# SCH_ELLIE_DISPLAY_PANEL.net
KiCad netlist of a schematic drawn in EasyEDA
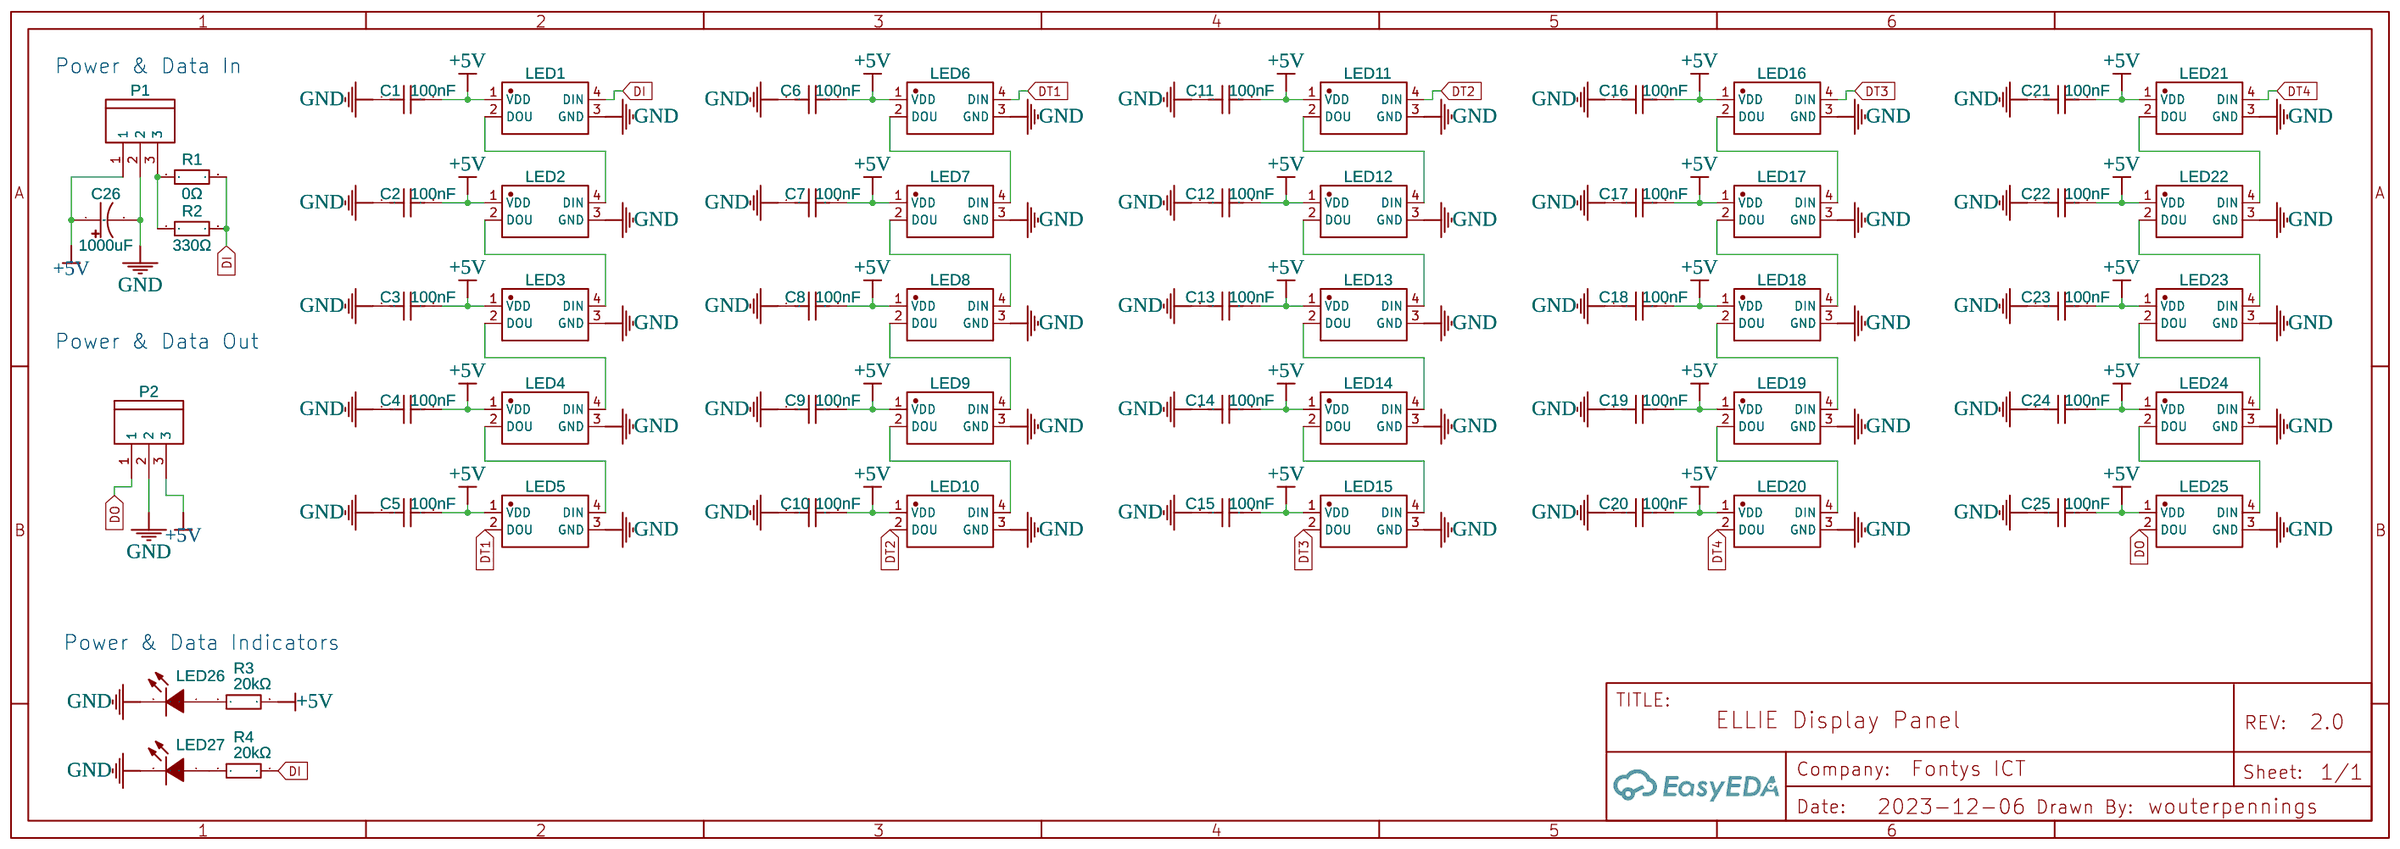
[diagram p0: schematic sheet]

(export (version "E")
  (design (tool "Eeschema 10.0.6"))
  (components
    (comp (ref "C1")
      (value "100nF")
      (fields
        (field (name "Manufacturer Part") "CC0402KRX7R7BB104")
        (field (name "Manufacturer") "YAGEO(国巨)")
      )
      (libsource (lib "") (part "CC0402KRX7R7BB104"))
    )
    (comp (ref "C2")
      (value "100nF")
      (fields
        (field (name "Manufacturer Part") "CC0402KRX7R7BB104")
        (field (name "Manufacturer") "YAGEO(国巨)")
      )
      (libsource (lib "") (part "CC0402KRX7R7BB104"))
    )
    (comp (ref "C3")
      (value "100nF")
      (fields
        (field (name "Manufacturer Part") "CC0402KRX7R7BB104")
        (field (name "Manufacturer") "YAGEO(国巨)")
      )
      (libsource (lib "") (part "CC0402KRX7R7BB104"))
    )
    (comp (ref "C4")
      (value "100nF")
      (fields
        (field (name "Manufacturer Part") "CC0402KRX7R7BB104")
        (field (name "Manufacturer") "YAGEO(国巨)")
      )
      (libsource (lib "") (part "CC0402KRX7R7BB104"))
    )
    (comp (ref "C5")
      (value "100nF")
      (fields
        (field (name "Manufacturer Part") "CC0402KRX7R7BB104")
        (field (name "Manufacturer") "YAGEO(国巨)")
      )
      (libsource (lib "") (part "CC0402KRX7R7BB104"))
    )
    (comp (ref "C6")
      (value "100nF")
      (fields
        (field (name "Manufacturer Part") "CC0402KRX7R7BB104")
        (field (name "Manufacturer") "YAGEO(国巨)")
      )
      (libsource (lib "") (part "CC0402KRX7R7BB104"))
    )
    (comp (ref "C7")
      (value "100nF")
      (fields
        (field (name "Manufacturer Part") "CC0402KRX7R7BB104")
        (field (name "Manufacturer") "YAGEO(国巨)")
      )
      (libsource (lib "") (part "CC0402KRX7R7BB104"))
    )
    (comp (ref "C8")
      (value "100nF")
      (fields
        (field (name "Manufacturer Part") "CC0402KRX7R7BB104")
        (field (name "Manufacturer") "YAGEO(国巨)")
      )
      (libsource (lib "") (part "CC0402KRX7R7BB104"))
    )
    (comp (ref "C9")
      (value "100nF")
      (fields
        (field (name "Manufacturer Part") "CC0402KRX7R7BB104")
        (field (name "Manufacturer") "YAGEO(国巨)")
      )
      (libsource (lib "") (part "CC0402KRX7R7BB104"))
    )
    (comp (ref "C10")
      (value "100nF")
      (fields
        (field (name "Manufacturer Part") "CC0402KRX7R7BB104")
        (field (name "Manufacturer") "YAGEO(国巨)")
      )
      (libsource (lib "") (part "CC0402KRX7R7BB104"))
    )
    (comp (ref "C11")
      (value "100nF")
      (fields
        (field (name "Manufacturer Part") "CC0402KRX7R7BB104")
        (field (name "Manufacturer") "YAGEO(国巨)")
      )
      (libsource (lib "") (part "CC0402KRX7R7BB104"))
    )
    (comp (ref "C12")
      (value "100nF")
      (fields
        (field (name "Manufacturer Part") "CC0402KRX7R7BB104")
        (field (name "Manufacturer") "YAGEO(国巨)")
      )
      (libsource (lib "") (part "CC0402KRX7R7BB104"))
    )
    (comp (ref "C13")
      (value "100nF")
      (fields
        (field (name "Manufacturer Part") "CC0402KRX7R7BB104")
        (field (name "Manufacturer") "YAGEO(国巨)")
      )
      (libsource (lib "") (part "CC0402KRX7R7BB104"))
    )
    (comp (ref "C14")
      (value "100nF")
      (fields
        (field (name "Manufacturer Part") "CC0402KRX7R7BB104")
        (field (name "Manufacturer") "YAGEO(国巨)")
      )
      (libsource (lib "") (part "CC0402KRX7R7BB104"))
    )
    (comp (ref "C15")
      (value "100nF")
      (fields
        (field (name "Manufacturer Part") "CC0402KRX7R7BB104")
        (field (name "Manufacturer") "YAGEO(国巨)")
      )
      (libsource (lib "") (part "CC0402KRX7R7BB104"))
    )
    (comp (ref "C16")
      (value "100nF")
      (fields
        (field (name "Manufacturer Part") "CC0402KRX7R7BB104")
        (field (name "Manufacturer") "YAGEO(国巨)")
      )
      (libsource (lib "") (part "CC0402KRX7R7BB104"))
    )
    (comp (ref "C17")
      (value "100nF")
      (fields
        (field (name "Manufacturer Part") "CC0402KRX7R7BB104")
        (field (name "Manufacturer") "YAGEO(国巨)")
      )
      (libsource (lib "") (part "CC0402KRX7R7BB104"))
    )
    (comp (ref "C18")
      (value "100nF")
      (fields
        (field (name "Manufacturer Part") "CC0402KRX7R7BB104")
        (field (name "Manufacturer") "YAGEO(国巨)")
      )
      (libsource (lib "") (part "CC0402KRX7R7BB104"))
    )
    (comp (ref "C19")
      (value "100nF")
      (fields
        (field (name "Manufacturer Part") "CC0402KRX7R7BB104")
        (field (name "Manufacturer") "YAGEO(国巨)")
      )
      (libsource (lib "") (part "CC0402KRX7R7BB104"))
    )
    (comp (ref "C20")
      (value "100nF")
      (fields
        (field (name "Manufacturer Part") "CC0402KRX7R7BB104")
        (field (name "Manufacturer") "YAGEO(国巨)")
      )
      (libsource (lib "") (part "CC0402KRX7R7BB104"))
    )
    (comp (ref "C21")
      (value "100nF")
      (fields
        (field (name "Manufacturer Part") "CC0402KRX7R7BB104")
        (field (name "Manufacturer") "YAGEO(国巨)")
      )
      (libsource (lib "") (part "CC0402KRX7R7BB104"))
    )
    (comp (ref "C22")
      (value "100nF")
      (fields
        (field (name "Manufacturer Part") "CC0402KRX7R7BB104")
        (field (name "Manufacturer") "YAGEO(国巨)")
      )
      (libsource (lib "") (part "CC0402KRX7R7BB104"))
    )
    (comp (ref "C23")
      (value "100nF")
      (fields
        (field (name "Manufacturer Part") "CC0402KRX7R7BB104")
        (field (name "Manufacturer") "YAGEO(国巨)")
      )
      (libsource (lib "") (part "CC0402KRX7R7BB104"))
    )
    (comp (ref "C24")
      (value "100nF")
      (fields
        (field (name "Manufacturer Part") "CC0402KRX7R7BB104")
        (field (name "Manufacturer") "YAGEO(国巨)")
      )
      (libsource (lib "") (part "CC0402KRX7R7BB104"))
    )
    (comp (ref "C25")
      (value "100nF")
      (fields
        (field (name "Manufacturer Part") "CC0402KRX7R7BB104")
        (field (name "Manufacturer") "YAGEO(国巨)")
      )
      (libsource (lib "") (part "CC0402KRX7R7BB104"))
    )
    (comp (ref "C26")
      (value "1000uF")
      (fields (field (name "Manufacturer Part") "VT1C102M1010") (field (name "Manufacturer") "ROQANG(容强)"))
      (libsource (lib "") (part "VT1C102M1010"))
    )
    (comp (ref "LED1")
      (value "XL-5050RGBC-WS2812B")
      (fields (field (name "Manufacturer") "XINGLIGHT(成兴光)"))
      (libsource (lib "") (part "XL-5050RGBC-WS2812B"))
    )
    (comp (ref "LED2")
      (value "XL-5050RGBC-WS2812B")
      (fields (field (name "Manufacturer") "XINGLIGHT(成兴光)"))
      (libsource (lib "") (part "XL-5050RGBC-WS2812B"))
    )
    (comp (ref "LED3")
      (value "XL-5050RGBC-WS2812B")
      (fields (field (name "Manufacturer") "XINGLIGHT(成兴光)"))
      (libsource (lib "") (part "XL-5050RGBC-WS2812B"))
    )
    (comp (ref "LED4")
      (value "XL-5050RGBC-WS2812B")
      (fields (field (name "Manufacturer") "XINGLIGHT(成兴光)"))
      (libsource (lib "") (part "XL-5050RGBC-WS2812B"))
    )
    (comp (ref "LED5")
      (value "XL-5050RGBC-WS2812B")
      (fields (field (name "Manufacturer") "XINGLIGHT(成兴光)"))
      (libsource (lib "") (part "XL-5050RGBC-WS2812B"))
    )
    (comp (ref "LED6")
      (value "XL-5050RGBC-WS2812B")
      (fields (field (name "Manufacturer") "XINGLIGHT(成兴光)"))
      (libsource (lib "") (part "XL-5050RGBC-WS2812B"))
    )
    (comp (ref "LED7")
      (value "XL-5050RGBC-WS2812B")
      (fields (field (name "Manufacturer") "XINGLIGHT(成兴光)"))
      (libsource (lib "") (part "XL-5050RGBC-WS2812B"))
    )
    (comp (ref "LED8")
      (value "XL-5050RGBC-WS2812B")
      (fields (field (name "Manufacturer") "XINGLIGHT(成兴光)"))
      (libsource (lib "") (part "XL-5050RGBC-WS2812B"))
    )
    (comp (ref "LED9")
      (value "XL-5050RGBC-WS2812B")
      (fields (field (name "Manufacturer") "XINGLIGHT(成兴光)"))
      (libsource (lib "") (part "XL-5050RGBC-WS2812B"))
    )
    (comp (ref "LED10")
      (value "XL-5050RGBC-WS2812B")
      (fields (field (name "Manufacturer") "XINGLIGHT(成兴光)"))
      (libsource (lib "") (part "XL-5050RGBC-WS2812B"))
    )
    (comp (ref "LED11")
      (value "XL-5050RGBC-WS2812B")
      (fields (field (name "Manufacturer") "XINGLIGHT(成兴光)"))
      (libsource (lib "") (part "XL-5050RGBC-WS2812B"))
    )
    (comp (ref "LED12")
      (value "XL-5050RGBC-WS2812B")
      (fields (field (name "Manufacturer") "XINGLIGHT(成兴光)"))
      (libsource (lib "") (part "XL-5050RGBC-WS2812B"))
    )
    (comp (ref "LED13")
      (value "XL-5050RGBC-WS2812B")
      (fields (field (name "Manufacturer") "XINGLIGHT(成兴光)"))
      (libsource (lib "") (part "XL-5050RGBC-WS2812B"))
    )
    (comp (ref "LED14")
      (value "XL-5050RGBC-WS2812B")
      (fields (field (name "Manufacturer") "XINGLIGHT(成兴光)"))
      (libsource (lib "") (part "XL-5050RGBC-WS2812B"))
    )
    (comp (ref "LED15")
      (value "XL-5050RGBC-WS2812B")
      (fields (field (name "Manufacturer") "XINGLIGHT(成兴光)"))
      (libsource (lib "") (part "XL-5050RGBC-WS2812B"))
    )
    (comp (ref "LED16")
      (value "XL-5050RGBC-WS2812B")
      (fields (field (name "Manufacturer") "XINGLIGHT(成兴光)"))
      (libsource (lib "") (part "XL-5050RGBC-WS2812B"))
    )
    (comp (ref "LED17")
      (value "XL-5050RGBC-WS2812B")
      (fields (field (name "Manufacturer") "XINGLIGHT(成兴光)"))
      (libsource (lib "") (part "XL-5050RGBC-WS2812B"))
    )
    (comp (ref "LED18")
      (value "XL-5050RGBC-WS2812B")
      (fields (field (name "Manufacturer") "XINGLIGHT(成兴光)"))
      (libsource (lib "") (part "XL-5050RGBC-WS2812B"))
    )
    (comp (ref "LED19")
      (value "XL-5050RGBC-WS2812B")
      (fields (field (name "Manufacturer") "XINGLIGHT(成兴光)"))
      (libsource (lib "") (part "XL-5050RGBC-WS2812B"))
    )
    (comp (ref "LED20")
      (value "XL-5050RGBC-WS2812B")
      (fields (field (name "Manufacturer") "XINGLIGHT(成兴光)"))
      (libsource (lib "") (part "XL-5050RGBC-WS2812B"))
    )
    (comp (ref "LED21")
      (value "XL-5050RGBC-WS2812B")
      (fields (field (name "Manufacturer") "XINGLIGHT(成兴光)"))
      (libsource (lib "") (part "XL-5050RGBC-WS2812B"))
    )
    (comp (ref "LED22")
      (value "XL-5050RGBC-WS2812B")
      (fields (field (name "Manufacturer") "XINGLIGHT(成兴光)"))
      (libsource (lib "") (part "XL-5050RGBC-WS2812B"))
    )
    (comp (ref "LED23")
      (value "XL-5050RGBC-WS2812B")
      (fields (field (name "Manufacturer") "XINGLIGHT(成兴光)"))
      (libsource (lib "") (part "XL-5050RGBC-WS2812B"))
    )
    (comp (ref "LED24")
      (value "XL-5050RGBC-WS2812B")
      (fields (field (name "Manufacturer") "XINGLIGHT(成兴光)"))
      (libsource (lib "") (part "XL-5050RGBC-WS2812B"))
    )
    (comp (ref "LED25")
      (value "XL-5050RGBC-WS2812B")
      (fields (field (name "Manufacturer") "XINGLIGHT(成兴光)"))
      (libsource (lib "") (part "XL-5050RGBC-WS2812B"))
    )
    (comp (ref "LED26")
      (value "SZYY0805R")
      (fields (field (name "Manufacturer") "yongyu(永裕光电)"))
      (libsource (lib "") (part "SZYY0805R"))
    )
    (comp (ref "LED27")
      (value "SZYY0805R")
      (fields (field (name "Manufacturer") "yongyu(永裕光电)"))
      (libsource (lib "") (part "SZYY0805R"))
    )
    (comp (ref "P1")
      (value "WJ500V-5.08-3P-14-00A")
      (fields
        (field (name "Manufacturer Part") "WJ500V-5.08-3P")
        (field (name "Manufacturer") "KANGNEX(康奈克斯电气)")
      )
      (libsource (lib "") (part "WJ500V-5.08-3P-14-00A"))
    )
    (comp (ref "P2")
      (value "WJ500V-5.08-3P-14-00A")
      (fields
        (field (name "Manufacturer Part") "WJ500V-5.08-3P")
        (field (name "Manufacturer") "KANGNEX(康奈克斯电气)")
      )
      (libsource (lib "") (part "WJ500V-5.08-3P-14-00A"))
    )
    (comp (ref "R1")
      (value "0Ω")
      (fields
        (field (name "Manufacturer Part") "0603WAF0000T5E")
        (field (name "Manufacturer") "UNI-ROYAL(厚声)")
      )
      (libsource (lib "") (part "0603WAF0000T5E"))
    )
    (comp (ref "R2")
      (value "330Ω")
      (fields (field (name "Manufacturer Part") "CF1/4W-330Ω±5% T") (field (name "Manufacturer") "CCO(千志电子)"))
      (libsource (lib "") (part "CF1/4W-330Ω±5% T52"))
    )
    (comp (ref "R3")
      (value "20kΩ")
      (fields
        (field (name "Manufacturer Part") "0603WAF2002T5E")
        (field (name "Manufacturer") "UNI-ROYAL(厚声)")
      )
      (libsource (lib "") (part "0603WAF2002T5E"))
    )
    (comp (ref "R4")
      (value "20kΩ")
      (fields
        (field (name "Manufacturer Part") "0603WAF2002T5E")
        (field (name "Manufacturer") "UNI-ROYAL(厚声)")
      )
      (libsource (lib "") (part "0603WAF2002T5E"))
    )
  )
  (nets
    (net (code "1") (name "+5V") (class "Default")
      (node (ref "C1") (pin "2") (pinfunction "2_2") (pintype "unspecified"))
      (node (ref "C10") (pin "2") (pinfunction "2_2") (pintype "unspecified"))
      (node (ref "C11") (pin "2") (pinfunction "2_2") (pintype "unspecified"))
      (node (ref "C12") (pin "2") (pinfunction "2_2") (pintype "unspecified"))
      (node (ref "C13") (pin "2") (pinfunction "2_2") (pintype "unspecified"))
      (node (ref "C14") (pin "2") (pinfunction "2_2") (pintype "unspecified"))
      (node (ref "C15") (pin "2") (pinfunction "2_2") (pintype "unspecified"))
      (node (ref "C16") (pin "2") (pinfunction "2_2") (pintype "unspecified"))
      (node (ref "C17") (pin "2") (pinfunction "2_2") (pintype "unspecified"))
      (node (ref "C18") (pin "2") (pinfunction "2_2") (pintype "unspecified"))
      (node (ref "C19") (pin "2") (pinfunction "2_2") (pintype "unspecified"))
      (node (ref "C2") (pin "2") (pinfunction "2_2") (pintype "unspecified"))
      (node (ref "C20") (pin "2") (pinfunction "2_2") (pintype "unspecified"))
      (node (ref "C21") (pin "2") (pinfunction "2_2") (pintype "unspecified"))
      (node (ref "C22") (pin "2") (pinfunction "2_2") (pintype "unspecified"))
      (node (ref "C23") (pin "2") (pinfunction "2_2") (pintype "unspecified"))
      (node (ref "C24") (pin "2") (pinfunction "2_2") (pintype "unspecified"))
      (node (ref "C25") (pin "2") (pinfunction "2_2") (pintype "unspecified"))
      (node (ref "C26") (pin "1") (pinfunction "1_1") (pintype "unspecified"))
      (node (ref "C3") (pin "2") (pinfunction "2_2") (pintype "unspecified"))
      (node (ref "C4") (pin "2") (pinfunction "2_2") (pintype "unspecified"))
      (node (ref "C5") (pin "2") (pinfunction "2_2") (pintype "unspecified"))
      (node (ref "C6") (pin "2") (pinfunction "2_2") (pintype "unspecified"))
      (node (ref "C7") (pin "2") (pinfunction "2_2") (pintype "unspecified"))
      (node (ref "C8") (pin "2") (pinfunction "2_2") (pintype "unspecified"))
      (node (ref "C9") (pin "2") (pinfunction "2_2") (pintype "unspecified"))
      (node (ref "LED1") (pin "1") (pinfunction "VDD_1") (pintype "unspecified"))
      (node (ref "LED10") (pin "1") (pinfunction "VDD_1") (pintype "unspecified"))
      (node (ref "LED11") (pin "1") (pinfunction "VDD_1") (pintype "unspecified"))
      (node (ref "LED12") (pin "1") (pinfunction "VDD_1") (pintype "unspecified"))
      (node (ref "LED13") (pin "1") (pinfunction "VDD_1") (pintype "unspecified"))
      (node (ref "LED14") (pin "1") (pinfunction "VDD_1") (pintype "unspecified"))
      (node (ref "LED15") (pin "1") (pinfunction "VDD_1") (pintype "unspecified"))
      (node (ref "LED16") (pin "1") (pinfunction "VDD_1") (pintype "unspecified"))
      (node (ref "LED17") (pin "1") (pinfunction "VDD_1") (pintype "unspecified"))
      (node (ref "LED18") (pin "1") (pinfunction "VDD_1") (pintype "unspecified"))
      (node (ref "LED19") (pin "1") (pinfunction "VDD_1") (pintype "unspecified"))
      (node (ref "LED2") (pin "1") (pinfunction "VDD_1") (pintype "unspecified"))
      (node (ref "LED20") (pin "1") (pinfunction "VDD_1") (pintype "unspecified"))
      (node (ref "LED21") (pin "1") (pinfunction "VDD_1") (pintype "unspecified"))
      (node (ref "LED22") (pin "1") (pinfunction "VDD_1") (pintype "unspecified"))
      (node (ref "LED23") (pin "1") (pinfunction "VDD_1") (pintype "unspecified"))
      (node (ref "LED24") (pin "1") (pinfunction "VDD_1") (pintype "unspecified"))
      (node (ref "LED25") (pin "1") (pinfunction "VDD_1") (pintype "unspecified"))
      (node (ref "LED3") (pin "1") (pinfunction "VDD_1") (pintype "unspecified"))
      (node (ref "LED4") (pin "1") (pinfunction "VDD_1") (pintype "unspecified"))
      (node (ref "LED5") (pin "1") (pinfunction "VDD_1") (pintype "unspecified"))
      (node (ref "LED6") (pin "1") (pinfunction "VDD_1") (pintype "unspecified"))
      (node (ref "LED7") (pin "1") (pinfunction "VDD_1") (pintype "unspecified"))
      (node (ref "LED8") (pin "1") (pinfunction "VDD_1") (pintype "unspecified"))
      (node (ref "LED9") (pin "1") (pinfunction "VDD_1") (pintype "unspecified"))
      (node (ref "P1") (pin "1") (pinfunction "1_1") (pintype "unspecified"))
      (node (ref "P2") (pin "3") (pinfunction "3_3") (pintype "unspecified"))
      (node (ref "R3") (pin "2") (pinfunction "2_2") (pintype "input"))
    )
    (net (code "2") (name "DI") (class "Default")
      (node (ref "LED1") (pin "4") (pinfunction "DIN_4") (pintype "unspecified"))
      (node (ref "R1") (pin "2") (pinfunction "2_2") (pintype "input"))
      (node (ref "R2") (pin "2") (pinfunction "2_2") (pintype "unspecified"))
      (node (ref "R4") (pin "2") (pinfunction "2_2") (pintype "input"))
    )
    (net (code "3") (name "DO") (class "Default")
      (node (ref "LED25") (pin "2") (pinfunction "DOU_2") (pintype "unspecified"))
      (node (ref "P2") (pin "1") (pinfunction "1_1") (pintype "unspecified"))
    )
    (net (code "4") (name "DT1") (class "Default")
      (node (ref "LED5") (pin "2") (pinfunction "DOU_2") (pintype "unspecified"))
      (node (ref "LED6") (pin "4") (pinfunction "DIN_4") (pintype "unspecified"))
    )
    (net (code "5") (name "DT2") (class "Default")
      (node (ref "LED10") (pin "2") (pinfunction "DOU_2") (pintype "unspecified"))
      (node (ref "LED11") (pin "4") (pinfunction "DIN_4") (pintype "unspecified"))
    )
    (net (code "6") (name "DT3") (class "Default")
      (node (ref "LED15") (pin "2") (pinfunction "DOU_2") (pintype "unspecified"))
      (node (ref "LED16") (pin "4") (pinfunction "DIN_4") (pintype "unspecified"))
    )
    (net (code "7") (name "DT4") (class "Default")
      (node (ref "LED20") (pin "2") (pinfunction "DOU_2") (pintype "unspecified"))
      (node (ref "LED21") (pin "4") (pinfunction "DIN_4") (pintype "unspecified"))
    )
    (net (code "8") (name "GND") (class "Default")
      (node (ref "C1") (pin "1") (pinfunction "1_1") (pintype "unspecified"))
      (node (ref "C10") (pin "1") (pinfunction "1_1") (pintype "unspecified"))
      (node (ref "C11") (pin "1") (pinfunction "1_1") (pintype "unspecified"))
      (node (ref "C12") (pin "1") (pinfunction "1_1") (pintype "unspecified"))
      (node (ref "C13") (pin "1") (pinfunction "1_1") (pintype "unspecified"))
      (node (ref "C14") (pin "1") (pinfunction "1_1") (pintype "unspecified"))
      (node (ref "C15") (pin "1") (pinfunction "1_1") (pintype "unspecified"))
      (node (ref "C16") (pin "1") (pinfunction "1_1") (pintype "unspecified"))
      (node (ref "C17") (pin "1") (pinfunction "1_1") (pintype "unspecified"))
      (node (ref "C18") (pin "1") (pinfunction "1_1") (pintype "unspecified"))
      (node (ref "C19") (pin "1") (pinfunction "1_1") (pintype "unspecified"))
      (node (ref "C2") (pin "1") (pinfunction "1_1") (pintype "unspecified"))
      (node (ref "C20") (pin "1") (pinfunction "1_1") (pintype "unspecified"))
      (node (ref "C21") (pin "1") (pinfunction "1_1") (pintype "unspecified"))
      (node (ref "C22") (pin "1") (pinfunction "1_1") (pintype "unspecified"))
      (node (ref "C23") (pin "1") (pinfunction "1_1") (pintype "unspecified"))
      (node (ref "C24") (pin "1") (pinfunction "1_1") (pintype "unspecified"))
      (node (ref "C25") (pin "1") (pinfunction "1_1") (pintype "unspecified"))
      (node (ref "C26") (pin "2") (pinfunction "2_2") (pintype "unspecified"))
      (node (ref "C3") (pin "1") (pinfunction "1_1") (pintype "unspecified"))
      (node (ref "C4") (pin "1") (pinfunction "1_1") (pintype "unspecified"))
      (node (ref "C5") (pin "1") (pinfunction "1_1") (pintype "unspecified"))
      (node (ref "C6") (pin "1") (pinfunction "1_1") (pintype "unspecified"))
      (node (ref "C7") (pin "1") (pinfunction "1_1") (pintype "unspecified"))
      (node (ref "C8") (pin "1") (pinfunction "1_1") (pintype "unspecified"))
      (node (ref "C9") (pin "1") (pinfunction "1_1") (pintype "unspecified"))
      (node (ref "LED1") (pin "3") (pinfunction "GND_3") (pintype "unspecified"))
      (node (ref "LED10") (pin "3") (pinfunction "GND_3") (pintype "unspecified"))
      (node (ref "LED11") (pin "3") (pinfunction "GND_3") (pintype "unspecified"))
      (node (ref "LED12") (pin "3") (pinfunction "GND_3") (pintype "unspecified"))
      (node (ref "LED13") (pin "3") (pinfunction "GND_3") (pintype "unspecified"))
      (node (ref "LED14") (pin "3") (pinfunction "GND_3") (pintype "unspecified"))
      (node (ref "LED15") (pin "3") (pinfunction "GND_3") (pintype "unspecified"))
      (node (ref "LED16") (pin "3") (pinfunction "GND_3") (pintype "unspecified"))
      (node (ref "LED17") (pin "3") (pinfunction "GND_3") (pintype "unspecified"))
      (node (ref "LED18") (pin "3") (pinfunction "GND_3") (pintype "unspecified"))
      (node (ref "LED19") (pin "3") (pinfunction "GND_3") (pintype "unspecified"))
      (node (ref "LED2") (pin "3") (pinfunction "GND_3") (pintype "unspecified"))
      (node (ref "LED20") (pin "3") (pinfunction "GND_3") (pintype "unspecified"))
      (node (ref "LED21") (pin "3") (pinfunction "GND_3") (pintype "unspecified"))
      (node (ref "LED22") (pin "3") (pinfunction "GND_3") (pintype "unspecified"))
      (node (ref "LED23") (pin "3") (pinfunction "GND_3") (pintype "unspecified"))
      (node (ref "LED24") (pin "3") (pinfunction "GND_3") (pintype "unspecified"))
      (node (ref "LED25") (pin "3") (pinfunction "GND_3") (pintype "unspecified"))
      (node (ref "LED26") (pin "2") (pinfunction "-_2") (pintype "unspecified"))
      (node (ref "LED27") (pin "2") (pinfunction "-_2") (pintype "unspecified"))
      (node (ref "LED3") (pin "3") (pinfunction "GND_3") (pintype "unspecified"))
      (node (ref "LED4") (pin "3") (pinfunction "GND_3") (pintype "unspecified"))
      (node (ref "LED5") (pin "3") (pinfunction "GND_3") (pintype "unspecified"))
      (node (ref "LED6") (pin "3") (pinfunction "GND_3") (pintype "unspecified"))
      (node (ref "LED7") (pin "3") (pinfunction "GND_3") (pintype "unspecified"))
      (node (ref "LED8") (pin "3") (pinfunction "GND_3") (pintype "unspecified"))
      (node (ref "LED9") (pin "3") (pinfunction "GND_3") (pintype "unspecified"))
      (node (ref "P1") (pin "2") (pinfunction "2_2") (pintype "unspecified"))
      (node (ref "P2") (pin "2") (pinfunction "2_2") (pintype "unspecified"))
    )
    (net (code "9") (name "Net-(LED1-DOU)") (class "Default")
      (node (ref "LED1") (pin "2") (pinfunction "DOU_2") (pintype "unspecified"))
      (node (ref "LED2") (pin "4") (pinfunction "DIN_4") (pintype "unspecified"))
    )
    (net (code "10") (name "Net-(LED2-DOU)") (class "Default")
      (node (ref "LED2") (pin "2") (pinfunction "DOU_2") (pintype "unspecified"))
      (node (ref "LED3") (pin "4") (pinfunction "DIN_4") (pintype "unspecified"))
    )
    (net (code "11") (name "Net-(LED3-DOU)") (class "Default")
      (node (ref "LED3") (pin "2") (pinfunction "DOU_2") (pintype "unspecified"))
      (node (ref "LED4") (pin "4") (pinfunction "DIN_4") (pintype "unspecified"))
    )
    (net (code "12") (name "Net-(LED4-DOU)") (class "Default")
      (node (ref "LED4") (pin "2") (pinfunction "DOU_2") (pintype "unspecified"))
      (node (ref "LED5") (pin "4") (pinfunction "DIN_4") (pintype "unspecified"))
    )
    (net (code "13") (name "Net-(LED6-DOU)") (class "Default")
      (node (ref "LED6") (pin "2") (pinfunction "DOU_2") (pintype "unspecified"))
      (node (ref "LED7") (pin "4") (pinfunction "DIN_4") (pintype "unspecified"))
    )
    (net (code "14") (name "Net-(LED7-DOU)") (class "Default")
      (node (ref "LED7") (pin "2") (pinfunction "DOU_2") (pintype "unspecified"))
      (node (ref "LED8") (pin "4") (pinfunction "DIN_4") (pintype "unspecified"))
    )
    (net (code "15") (name "Net-(LED8-DOU)") (class "Default")
      (node (ref "LED8") (pin "2") (pinfunction "DOU_2") (pintype "unspecified"))
      (node (ref "LED9") (pin "4") (pinfunction "DIN_4") (pintype "unspecified"))
    )
    (net (code "16") (name "Net-(LED10-DIN)") (class "Default")
      (node (ref "LED10") (pin "4") (pinfunction "DIN_4") (pintype "unspecified"))
      (node (ref "LED9") (pin "2") (pinfunction "DOU_2") (pintype "unspecified"))
    )
    (net (code "17") (name "Net-(LED11-DOU)") (class "Default")
      (node (ref "LED11") (pin "2") (pinfunction "DOU_2") (pintype "unspecified"))
      (node (ref "LED12") (pin "4") (pinfunction "DIN_4") (pintype "unspecified"))
    )
    (net (code "18") (name "Net-(LED12-DOU)") (class "Default")
      (node (ref "LED12") (pin "2") (pinfunction "DOU_2") (pintype "unspecified"))
      (node (ref "LED13") (pin "4") (pinfunction "DIN_4") (pintype "unspecified"))
    )
    (net (code "19") (name "Net-(LED13-DOU)") (class "Default")
      (node (ref "LED13") (pin "2") (pinfunction "DOU_2") (pintype "unspecified"))
      (node (ref "LED14") (pin "4") (pinfunction "DIN_4") (pintype "unspecified"))
    )
    (net (code "20") (name "Net-(LED14-DOU)") (class "Default")
      (node (ref "LED14") (pin "2") (pinfunction "DOU_2") (pintype "unspecified"))
      (node (ref "LED15") (pin "4") (pinfunction "DIN_4") (pintype "unspecified"))
    )
    (net (code "21") (name "Net-(LED16-DOU)") (class "Default")
      (node (ref "LED16") (pin "2") (pinfunction "DOU_2") (pintype "unspecified"))
      (node (ref "LED17") (pin "4") (pinfunction "DIN_4") (pintype "unspecified"))
    )
    (net (code "22") (name "Net-(LED17-DOU)") (class "Default")
      (node (ref "LED17") (pin "2") (pinfunction "DOU_2") (pintype "unspecified"))
      (node (ref "LED18") (pin "4") (pinfunction "DIN_4") (pintype "unspecified"))
    )
    (net (code "23") (name "Net-(LED18-DOU)") (class "Default")
      (node (ref "LED18") (pin "2") (pinfunction "DOU_2") (pintype "unspecified"))
      (node (ref "LED19") (pin "4") (pinfunction "DIN_4") (pintype "unspecified"))
    )
    (net (code "24") (name "Net-(LED19-DOU)") (class "Default")
      (node (ref "LED19") (pin "2") (pinfunction "DOU_2") (pintype "unspecified"))
      (node (ref "LED20") (pin "4") (pinfunction "DIN_4") (pintype "unspecified"))
    )
    (net (code "25") (name "Net-(LED21-DOU)") (class "Default")
      (node (ref "LED21") (pin "2") (pinfunction "DOU_2") (pintype "unspecified"))
      (node (ref "LED22") (pin "4") (pinfunction "DIN_4") (pintype "unspecified"))
    )
    (net (code "26") (name "Net-(LED22-DOU)") (class "Default")
      (node (ref "LED22") (pin "2") (pinfunction "DOU_2") (pintype "unspecified"))
      (node (ref "LED23") (pin "4") (pinfunction "DIN_4") (pintype "unspecified"))
    )
    (net (code "27") (name "Net-(LED23-DOU)") (class "Default")
      (node (ref "LED23") (pin "2") (pinfunction "DOU_2") (pintype "unspecified"))
      (node (ref "LED24") (pin "4") (pinfunction "DIN_4") (pintype "unspecified"))
    )
    (net (code "28") (name "Net-(LED24-DOU)") (class "Default")
      (node (ref "LED24") (pin "2") (pinfunction "DOU_2") (pintype "unspecified"))
      (node (ref "LED25") (pin "4") (pinfunction "DIN_4") (pintype "unspecified"))
    )
    (net (code "29") (name "Net-(LED26-+)") (class "Default")
      (node (ref "LED26") (pin "1") (pinfunction "+_1") (pintype "unspecified"))
      (node (ref "R3") (pin "1") (pinfunction "1_1") (pintype "input"))
    )
    (net (code "30") (name "Net-(LED27-+)") (class "Default")
      (node (ref "LED27") (pin "1") (pinfunction "+_1") (pintype "unspecified"))
      (node (ref "R4") (pin "1") (pinfunction "1_1") (pintype "input"))
    )
    (net (code "31") (name "Net-(P1-Pad3)") (class "Default")
      (node (ref "P1") (pin "3") (pinfunction "3_3") (pintype "unspecified"))
      (node (ref "R1") (pin "1") (pinfunction "1_1") (pintype "input"))
      (node (ref "R2") (pin "1") (pinfunction "1_1") (pintype "unspecified"))
    )
  )
)
